# Power.net
KiCad netlist of a schematic drawn in Altium Designer
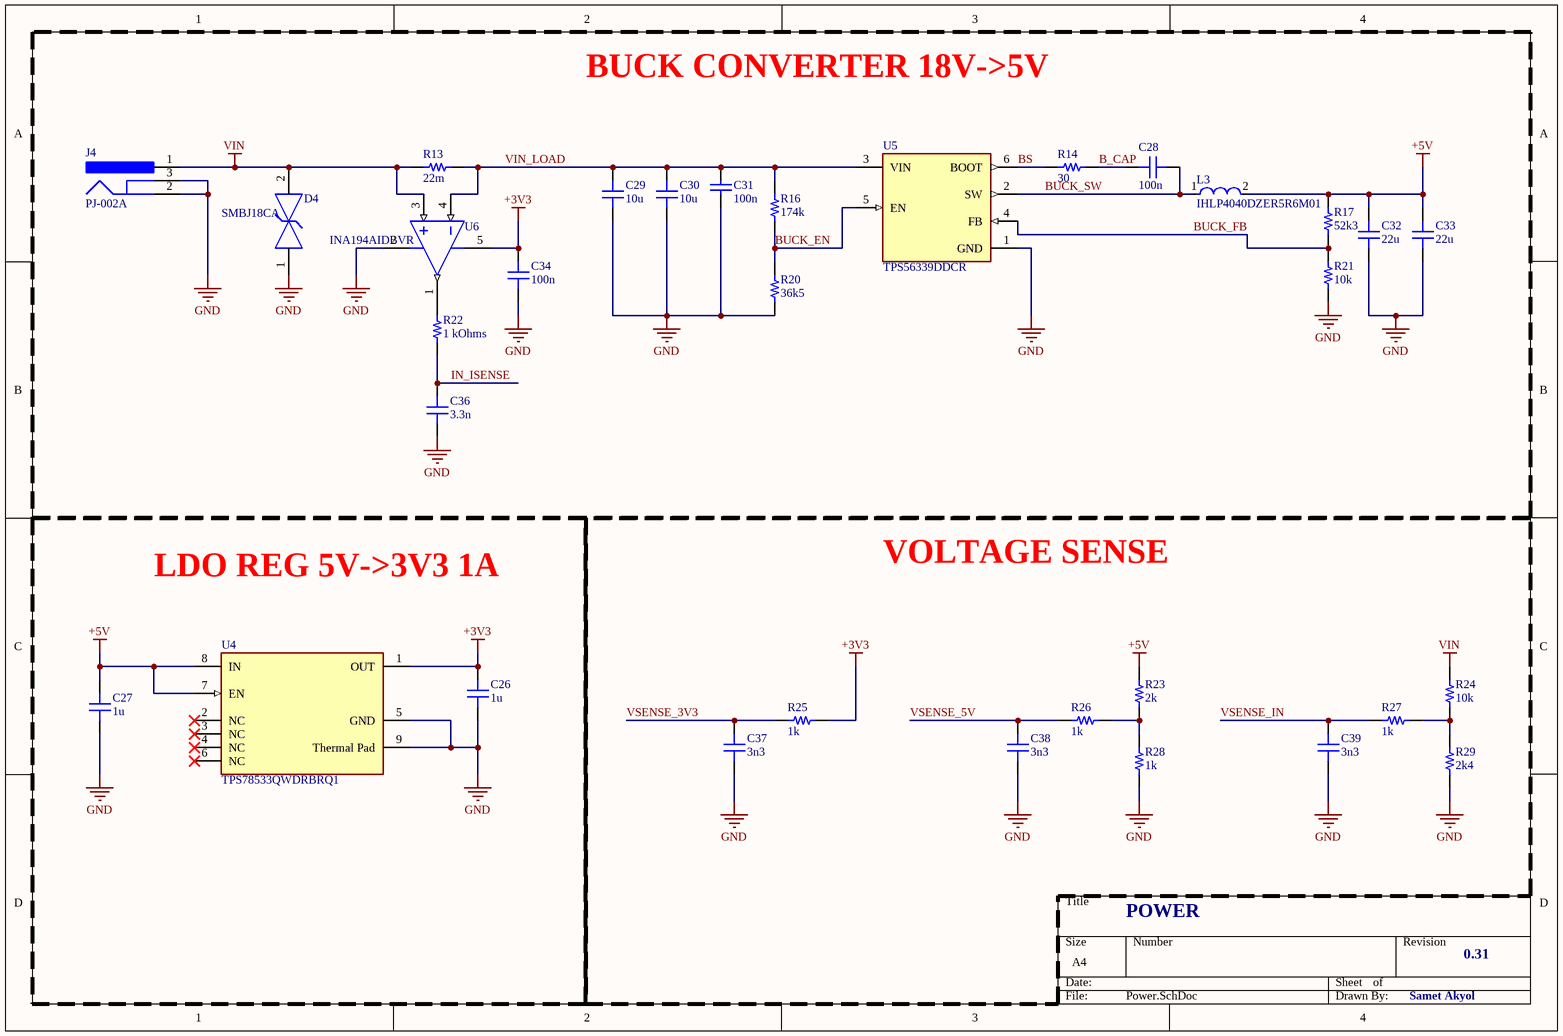
[diagram p0: Power.SchDoc]

(export (version "E")
  (design (tool "Eeschema 10.0.6"))
  (components
    (comp (ref "C26")
      (value "1u")
      (footprint "CAP 0603_1608")
      (description "CAP CER 10UF 16V X5R 0603")
      (fields
        (field (name "PART NUMBER") "GRT188R61C106ME13D")
        (field (name "MANUFACTURER") "Murata Electronics")
      )
      (libsource (lib "Celestial Altium Library - altium_library") (part "Capacitor"))
    )
    (comp (ref "C27")
      (value "1u")
      (footprint "CAP 0603_1608")
      (description "CAP CER 1UF 16V X5R 0603")
      (fields (field (name "PART NUMBER") "0603YD105MAT2A") (field (name "MANUFACTURER") "AVX Corporation"))
      (libsource (lib "Celestial Altium Library - altium_library") (part "Capacitor"))
    )
    (comp (ref "C28")
      (value "100n")
      (footprint "CAP 0603_1608")
      (description "CAP CER 10UF 10V X5R 0603")
      (fields
        (field (name "PART NUMBER") "MD0603BW106M100NHT-EM")
        (field (name "MANUFACTURER") "Knowles Novacap")
      )
      (libsource (lib "Celestial Altium Library - altium_library") (part "Capacitor"))
    )
    (comp (ref "C29")
      (value "10u")
      (footprint "CAP 0805_2012")
      (description "CAP CER 10UF 16V X6S 0805")
      (fields
        (field (name "PART NUMBER") "C2012X6S1C106K125AC")
        (field (name "MANUFACTURER") "TDK Corporation")
      )
      (libsource (lib "Celestial Altium Library - altium_library") (part "Capacitor"))
    )
    (comp (ref "C30")
      (value "10u")
      (footprint "CAP 0805_2012")
      (description "CAP CER 10UF 16V X6S 0805")
      (fields
        (field (name "PART NUMBER") "C2012X6S1C106K125AC")
        (field (name "MANUFACTURER") "TDK Corporation")
      )
      (libsource (lib "Celestial Altium Library - altium_library") (part "Capacitor"))
    )
    (comp (ref "C31")
      (value "100n")
      (footprint "CAPC2013X145X20LL20")
      (description "Chip Capacitor, 0.1 uF, +/- 10%, 50 V, -55 to 125 degC, 0805 (2012 Metric), RoHS, Tape and Reel")
      (fields (field (name "MANUFACTURER") "TDK") (field (name "VOLTAGE") "50V"))
      (libsource (lib "Altium Content Vault") (part "CAP-NP-2"))
    )
    (comp (ref "C32")
      (value "22u")
      (footprint "CAP 0805_2012")
      (description "CAP CER 22UF 16V X5R 0805")
      (fields
        (field (name "PART NUMBER") "CL21A226KOQNNNG")
        (field (name "MANUFACTURER") "Samsung Electro-Mechanics")
      )
      (libsource (lib "Celestial Altium Library - altium_library") (part "Capacitor"))
    )
    (comp (ref "C33")
      (value "22u")
      (footprint "CAP 0805_2012")
      (description "CAP CER 22UF 16V X5R 0805")
      (fields
        (field (name "PART NUMBER") "CL21A226KOQNNNG")
        (field (name "MANUFACTURER") "Samsung Electro-Mechanics")
      )
      (libsource (lib "Celestial Altium Library - altium_library") (part "Capacitor"))
    )
    (comp (ref "C34")
      (value "100n")
      (footprint "CAP 0402_1005")
      (description "CAP CER 1UF 10V X7S 0402")
      (fields
        (field (name "PART NUMBER") "GRM155C71A105KE11D")
        (field (name "MANUFACTURER") "Murata Electronics")
      )
      (libsource (lib "Celestial Altium Library - altium_library") (part "Capacitor"))
    )
    (comp (ref "C36")
      (value "3.3n")
      (footprint "CAP 0402_1005")
      (description "CAP CER 1UF 10V X7S 0402")
      (fields
        (field (name "PART NUMBER") "GRM155C71A105KE11D")
        (field (name "MANUFACTURER") "Murata Electronics")
      )
      (libsource (lib "Celestial Altium Library - altium_library") (part "Capacitor"))
    )
    (comp (ref "C37")
      (value "3n3")
      (footprint "CAP 0402_1005")
      (description "CAP CER 1UF 10V X7S 0402")
      (fields
        (field (name "PART NUMBER") "GRM155C71A105KE11D")
        (field (name "MANUFACTURER") "Murata Electronics")
      )
      (libsource (lib "Celestial Altium Library - altium_library") (part "Capacitor"))
    )
    (comp (ref "C38")
      (value "3n3")
      (footprint "CAP 0402_1005")
      (description "CAP CER 1UF 10V X7S 0402")
      (fields
        (field (name "PART NUMBER") "GRM155C71A105KE11D")
        (field (name "MANUFACTURER") "Murata Electronics")
      )
      (libsource (lib "Celestial Altium Library - altium_library") (part "Capacitor"))
    )
    (comp (ref "C39")
      (value "3n3")
      (footprint "CAP 0402_1005")
      (description "CAP CER 1UF 10V X7S 0402")
      (fields
        (field (name "PART NUMBER") "GRM155C71A105KE11D")
        (field (name "MANUFACTURER") "Murata Electronics")
      )
      (libsource (lib "Celestial Altium Library - altium_library") (part "Capacitor"))
    )
    (comp (ref "D4")
      (value "SMBJ18CA")
      (footprint "FP-SMBJ-MFG")
      (description "TVS DIODE 18V 29.2V DO214AA")
      (fields
        (field (name "MANUFACTURER") "Littelfuse Inc")
        (field (name "OCTOPART") "https://octopart.com/smbj18ca-littelfuse-350695")
      )
      (libsource (lib "Altium Content Vault") (part "876f4347bf90aa6f500f43e3cd03972"))
    )
    (comp (ref "J4")
      (value "PJ-002A")
      (footprint "CUI-PJ-002A_V")
      (fields (field (name "MANUFACTURER") "CUIInc."))
      (libsource (lib "Altium Content Vault") (part "JACK-2CD3-RN_B"))
    )
    (comp (ref "L3")
      (value "IHLP4040DZER5R6M01")
      (footprint "FP-IHLP-4040DZ-FP_3_124x3-MFG")
      (description "Commercial Inductors, High Saturation Series 5.6uH 8.5A 19.3mΩ 20%")
      (fields (field (name "TOLERANCE") "20%"))
      (libsource (lib "Altium Content Vault") (part "725321dda6339637d4d059423bc1c3c"))
    )
    (comp (ref "R13")
      (value "22m")
      (footprint "STACKPOLE CSM2512")
      (description "RES 0.022 OHM 1% 3W 2512")
      (fields
        (field (name "PART NUMBER") "CSM2512FT22L0")
        (field (name "MANUFACTURER") "Stackpole Electronics Inc")
      )
      (libsource (lib "Celestial Altium Library - altium_library") (part "Resistor"))
    )
    (comp (ref "R14")
      (value "30")
      (footprint "RES 0402_1005")
      (description "RES SMD 1K OHM 0.1% 1/16W 0402")
      (fields
        (field (name "PART NUMBER") "CPF0402B1K0E")
        (field (name "MANUFACTURER") "TE Connectivity Passive Product")
      )
      (libsource (lib "Celestial Altium Library - altium_library") (part "Resistor"))
    )
    (comp (ref "R16")
      (value "174k")
      (footprint "RES 0402_1005")
      (description "RES 174K OHM 0.1% 1/10W 0402")
      (fields
        (field (name "PART NUMBER") "RP73PF1E174KBTD")
        (field (name "MANUFACTURER") "TE Connectivity Passive Product")
      )
      (libsource (lib "Celestial Altium Library - altium_library") (part "Resistor"))
    )
    (comp (ref "R17")
      (value "52k3")
      (footprint "RES 0603_1608")
      (description "RES 10K OHM 0.1% 1/16W 0603")
      (fields
        (field (name "PART NUMBER") "RNCS0603BKE10K0")
        (field (name "MANUFACTURER") "Stackpole Electronics Inc")
      )
      (libsource (lib "Celestial Altium Library - altium_library") (part "Resistor"))
    )
    (comp (ref "R20")
      (value "36k5")
      (footprint "RES 0402_1005")
      (description "RES SMD 36.5KOHM 0.1% 1/16W 0402")
      (fields
        (field (name "PART NUMBER") "RN73C1E36K5BTD")
        (field (name "MANUFACTURER") "TE Connectivity Passive Product")
      )
      (libsource (lib "Celestial Altium Library - altium_library") (part "Resistor"))
    )
    (comp (ref "R21")
      (value "10k")
      (footprint "RES 0603_1608")
      (description "RES 10K OHM 0.1% 1/16W 0603")
      (fields
        (field (name "PART NUMBER") "RNCS0603BKE10K0")
        (field (name "MANUFACTURER") "Stackpole Electronics Inc")
      )
      (libsource (lib "Celestial Altium Library - altium_library") (part "Resistor"))
    )
    (comp (ref "R22")
      (value "1 kOhms")
      (footprint "RES 0402_1005")
      (description "RES SMD 1K OHM 0.1% 1/16W 0402")
      (fields
        (field (name "PART NUMBER") "CPF0402B1K0E")
        (field (name "MANUFACTURER") "TE Connectivity Passive Product")
      )
      (libsource (lib "Celestial Altium Library - altium_library") (part "Resistor"))
    )
    (comp (ref "R23")
      (value "2k")
      (footprint "RES 0402_1005")
      (description "RES SMD 1K OHM 0.1% 1/16W 0402")
      (fields
        (field (name "PART NUMBER") "CPF0402B1K0E")
        (field (name "MANUFACTURER") "TE Connectivity Passive Product")
      )
      (libsource (lib "Celestial Altium Library - altium_library") (part "Resistor"))
    )
    (comp (ref "R24")
      (value "10k")
      (footprint "RES 0402_1005")
      (description "RES SMD 1K OHM 0.1% 1/16W 0402")
      (fields
        (field (name "PART NUMBER") "CPF0402B1K0E")
        (field (name "MANUFACTURER") "TE Connectivity Passive Product")
      )
      (libsource (lib "Celestial Altium Library - altium_library") (part "Resistor"))
    )
    (comp (ref "R25")
      (value "1k")
      (footprint "RES 0402_1005")
      (description "RES SMD 1K OHM 0.1% 1/16W 0402")
      (fields
        (field (name "PART NUMBER") "CPF0402B1K0E")
        (field (name "MANUFACTURER") "TE Connectivity Passive Product")
      )
      (libsource (lib "Celestial Altium Library - altium_library") (part "Resistor"))
    )
    (comp (ref "R26")
      (value "1k")
      (footprint "RES 0402_1005")
      (description "RES SMD 1K OHM 0.1% 1/16W 0402")
      (fields
        (field (name "PART NUMBER") "CPF0402B1K0E")
        (field (name "MANUFACTURER") "TE Connectivity Passive Product")
      )
      (libsource (lib "Celestial Altium Library - altium_library") (part "Resistor"))
    )
    (comp (ref "R27")
      (value "1k")
      (footprint "RES 0402_1005")
      (description "RES SMD 1K OHM 0.1% 1/16W 0402")
      (fields
        (field (name "PART NUMBER") "CPF0402B1K0E")
        (field (name "MANUFACTURER") "TE Connectivity Passive Product")
      )
      (libsource (lib "Celestial Altium Library - altium_library") (part "Resistor"))
    )
    (comp (ref "R28")
      (value "1k")
      (footprint "RES 0402_1005")
      (description "RES SMD 1K OHM 0.1% 1/16W 0402")
      (fields
        (field (name "PART NUMBER") "CPF0402B1K0E")
        (field (name "MANUFACTURER") "TE Connectivity Passive Product")
      )
      (libsource (lib "Celestial Altium Library - altium_library") (part "Resistor"))
    )
    (comp (ref "R29")
      (value "2k4")
      (footprint "RES 0402_1005")
      (description "RES SMD 1K OHM 0.1% 1/16W 0402")
      (fields
        (field (name "PART NUMBER") "CPF0402B1K0E")
        (field (name "MANUFACTURER") "TE Connectivity Passive Product")
      )
      (libsource (lib "Celestial Altium Library - altium_library") (part "Resistor"))
    )
    (comp (ref "U4")
      (value "TPS78533QWDRBRQ1")
      (footprint "FP-DRB0008J-MFG")
      (libsource (lib "Altium Content Vault") (part "e9cafef991045e92127502b1f141fdc"))
    )
    (comp (ref "U5")
      (value "TPS56339DDCR")
      (footprint "FP-DDC0006A-MFG")
      (description "PWR MGMT SPECIALIZED REGULATOR")
      (fields
        (field (name "MANUFACTURER") "Texas Instruments")
        (field (name "OCTOPART") "https://octopart.com/tps56339ddcr-texas+instruments-101466410")
      )
      (libsource (lib "Altium Content Vault") (part "2ef13c8a92b2ccd2de8c1984d71b5d5"))
    )
    (comp (ref "U6")
      (value "INA194AIDBVR")
      (footprint "DBV0005A_M")
      (fields (field (name "MANUFACTURER") "Texas Instruments"))
      (libsource (lib "Altium Content Vault") (part "TI-INA1XXDBV5"))
    )
  )
  (nets
    (net (code "1") (name "+3V3") (class "Default")
      (node (ref "C26") (pin "2") (pinfunction "2_2") (pintype "passive"))
      (node (ref "C34") (pin "2") (pinfunction "2_2") (pintype "passive"))
      (node (ref "R25") (pin "2") (pinfunction "2_2") (pintype "passive"))
      (node (ref "U4") (pin "1") (pinfunction "OUT_1") (pintype "power_in"))
      (node (ref "U6") (pin "5") (pinfunction "V+_5") (pintype "power_in"))
    )
    (net (code "2") (name "+5V") (class "Default")
      (node (ref "C27") (pin "2") (pinfunction "2_2") (pintype "passive"))
      (node (ref "C32") (pin "2") (pinfunction "2_2") (pintype "passive"))
      (node (ref "C33") (pin "2") (pinfunction "2_2") (pintype "passive"))
      (node (ref "L3") (pin "2") (pinfunction "2_2") (pintype "passive"))
      (node (ref "R17") (pin "2") (pinfunction "2_2") (pintype "passive"))
      (node (ref "R23") (pin "1") (pinfunction "1_1") (pintype "passive"))
      (node (ref "U4") (pin "7") (pinfunction "EN_7") (pintype "input"))
      (node (ref "U4") (pin "8") (pinfunction "IN_8") (pintype "power_in"))
    )
    (net (code "3") (name "/BS") (class "Default")
      (node (ref "R14") (pin "2") (pinfunction "2_2") (pintype "passive"))
      (node (ref "U5") (pin "6") (pinfunction "BOOT_6") (pintype "output"))
    )
    (net (code "4") (name "/BUCK_EN") (class "Default")
      (node (ref "R16") (pin "1") (pinfunction "1_1") (pintype "passive"))
      (node (ref "R20") (pin "2") (pinfunction "2_2") (pintype "passive"))
      (node (ref "U5") (pin "5") (pinfunction "EN_5") (pintype "input"))
    )
    (net (code "5") (name "/BUCK_FB") (class "Default")
      (node (ref "R17") (pin "1") (pinfunction "1_1") (pintype "passive"))
      (node (ref "R21") (pin "2") (pinfunction "2_2") (pintype "passive"))
      (node (ref "U5") (pin "4") (pinfunction "FB_4") (pintype "input"))
    )
    (net (code "6") (name "/BUCK_SW") (class "Default")
      (node (ref "C28") (pin "2") (pinfunction "2_2") (pintype "passive"))
      (node (ref "L3") (pin "1") (pinfunction "1_1") (pintype "passive"))
      (node (ref "U5") (pin "2") (pinfunction "SW_2") (pintype "output"))
    )
    (net (code "7") (name "/B_CAP") (class "Default")
      (node (ref "C28") (pin "1") (pinfunction "1_1") (pintype "passive"))
      (node (ref "R14") (pin "1") (pinfunction "1_1") (pintype "passive"))
    )
    (net (code "8") (name "/IN_ISENSE") (class "Default")
      (node (ref "C36") (pin "2") (pinfunction "2_2") (pintype "passive"))
      (node (ref "R22") (pin "1") (pinfunction "1_1") (pintype "passive"))
    )
    (net (code "9") (name "/VIN_LOAD") (class "Default")
      (node (ref "C29") (pin "2") (pinfunction "2_2") (pintype "passive"))
      (node (ref "C30") (pin "2") (pinfunction "2_2") (pintype "passive"))
      (node (ref "C31") (pin "2") (pinfunction "2_2") (pintype "passive"))
      (node (ref "R13") (pin "2") (pinfunction "2_2") (pintype "passive"))
      (node (ref "R16") (pin "2") (pinfunction "2_2") (pintype "passive"))
      (node (ref "U5") (pin "3") (pinfunction "VIN_3") (pintype "power_in"))
      (node (ref "U6") (pin "4") (pinfunction "VIN-_4") (pintype "input"))
    )
    (net (code "10") (name "/VSENSE_3V3") (class "Default")
      (node (ref "C37") (pin "2") (pinfunction "2_2") (pintype "passive"))
      (node (ref "R25") (pin "1") (pinfunction "1_1") (pintype "passive"))
    )
    (net (code "11") (name "/VSENSE_5V") (class "Default")
      (node (ref "C38") (pin "2") (pinfunction "2_2") (pintype "passive"))
      (node (ref "R26") (pin "1") (pinfunction "1_1") (pintype "passive"))
    )
    (net (code "12") (name "/VSENSE_IN") (class "Default")
      (node (ref "C39") (pin "2") (pinfunction "2_2") (pintype "passive"))
      (node (ref "R27") (pin "1") (pinfunction "1_1") (pintype "passive"))
    )
    (net (code "13") (name "GND") (class "Default")
      (node (ref "C26") (pin "1") (pinfunction "1_1") (pintype "passive"))
      (node (ref "C27") (pin "1") (pinfunction "1_1") (pintype "passive"))
      (node (ref "C29") (pin "1") (pinfunction "1_1") (pintype "passive"))
      (node (ref "C30") (pin "1") (pinfunction "1_1") (pintype "passive"))
      (node (ref "C31") (pin "1") (pinfunction "1_1") (pintype "passive"))
      (node (ref "C32") (pin "1") (pinfunction "1_1") (pintype "passive"))
      (node (ref "C33") (pin "1") (pinfunction "1_1") (pintype "passive"))
      (node (ref "C34") (pin "1") (pinfunction "1_1") (pintype "passive"))
      (node (ref "C36") (pin "1") (pinfunction "1_1") (pintype "passive"))
      (node (ref "C37") (pin "1") (pinfunction "1_1") (pintype "passive"))
      (node (ref "C38") (pin "1") (pinfunction "1_1") (pintype "passive"))
      (node (ref "C39") (pin "1") (pinfunction "1_1") (pintype "passive"))
      (node (ref "D4") (pin "1") (pinfunction "1_1") (pintype "passive"))
      (node (ref "J4") (pin "2") (pinfunction "2_2") (pintype "passive"))
      (node (ref "J4") (pin "3") (pinfunction "3_3") (pintype "passive"))
      (node (ref "R20") (pin "1") (pinfunction "1_1") (pintype "passive"))
      (node (ref "R21") (pin "1") (pinfunction "1_1") (pintype "passive"))
      (node (ref "R28") (pin "2") (pinfunction "2_2") (pintype "passive"))
      (node (ref "R29") (pin "2") (pinfunction "2_2") (pintype "passive"))
      (node (ref "U4") (pin "5") (pinfunction "GND_5") (pintype "power_in"))
      (node (ref "U4") (pin "9") (pinfunction "Thermal_Pad_9") (pintype "power_in"))
      (node (ref "U5") (pin "1") (pinfunction "GND_1") (pintype "power_in"))
      (node (ref "U6") (pin "2") (pinfunction "GND_2") (pintype "power_in"))
    )
    (net (code "14") (name "Net-(R23-Pad2)") (class "Default")
      (node (ref "R23") (pin "2") (pinfunction "2_2") (pintype "passive"))
      (node (ref "R26") (pin "2") (pinfunction "2_2") (pintype "passive"))
      (node (ref "R28") (pin "1") (pinfunction "1_1") (pintype "passive"))
    )
    (net (code "15") (name "Net-(R24-Pad2)") (class "Default")
      (node (ref "R24") (pin "2") (pinfunction "2_2") (pintype "passive"))
      (node (ref "R27") (pin "2") (pinfunction "2_2") (pintype "passive"))
      (node (ref "R29") (pin "1") (pinfunction "1_1") (pintype "passive"))
    )
    (net (code "16") (name "Net-(U6-OUT)") (class "Default")
      (node (ref "R22") (pin "2") (pinfunction "2_2") (pintype "passive"))
      (node (ref "U6") (pin "1") (pinfunction "OUT_1") (pintype "output"))
    )
    (net (code "17") (name "VIN") (class "Default")
      (node (ref "D4") (pin "2") (pinfunction "2_2") (pintype "passive"))
      (node (ref "J4") (pin "1") (pinfunction "1_1") (pintype "passive"))
      (node (ref "R13") (pin "1") (pinfunction "1_1") (pintype "passive"))
      (node (ref "R24") (pin "1") (pinfunction "1_1") (pintype "passive"))
      (node (ref "U6") (pin "3") (pinfunction "VIN+_3") (pintype "input"))
    )
    (net (code "18") (name "unconnected-(U4-NC-Pad2)") (class "Default")
      (node (ref "U4") (pin "2") (pinfunction "NC_2") (pintype "passive+no_connect"))
    )
    (net (code "19") (name "unconnected-(U4-NC-Pad3)") (class "Default")
      (node (ref "U4") (pin "3") (pinfunction "NC_3") (pintype "passive+no_connect"))
    )
    (net (code "20") (name "unconnected-(U4-NC-Pad4)") (class "Default")
      (node (ref "U4") (pin "4") (pinfunction "NC_4") (pintype "passive+no_connect"))
    )
    (net (code "21") (name "unconnected-(U4-NC-Pad6)") (class "Default")
      (node (ref "U4") (pin "6") (pinfunction "NC_6") (pintype "passive+no_connect"))
    )
  )
)
